# Bpod_PortBreakout_r1.net
KiCad netlist of a schematic drawn in EAGLE
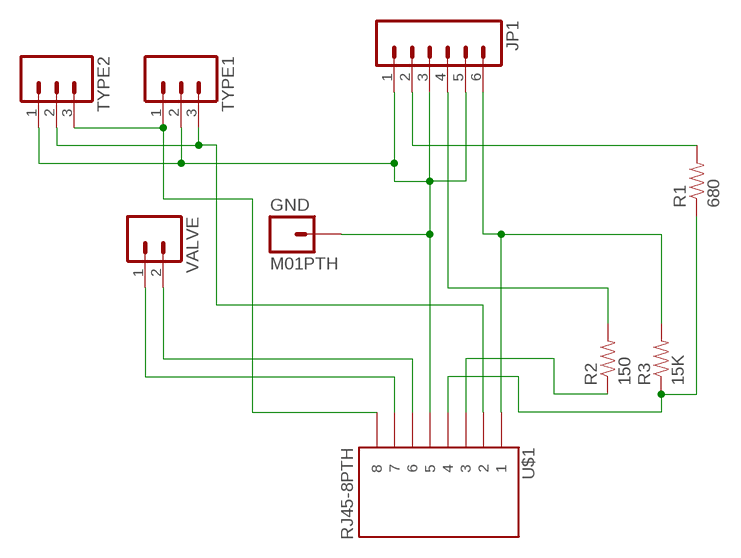
[diagram p0: schematic, sheet 1]

(export (version "E")
  (design (tool "Eeschema 10.0.6"))
  (components
    (comp (ref "GND")
      (value "M01PTH")
      (footprint "eagle-import:1X01")
      (libsource (lib "eagle-import") (part "M01PTH"))
    )
    (comp (ref "JP1")
      (value "M063.5MM-6")
      (footprint "eagle-import:SCREWTERMINAL-3.5MM-6")
      (libsource (lib "eagle-import") (part "M063.5MM-6"))
    )
    (comp (ref "R1")
      (value "680")
      (footprint "eagle-import:AXIAL-0.4")
      (libsource (lib "eagle-import") (part "RESISTORPTH-1/4W"))
    )
    (comp (ref "R2")
      (value "150")
      (footprint "eagle-import:AXIAL-0.4")
      (libsource (lib "eagle-import") (part "RESISTORPTH-1/4W"))
    )
    (comp (ref "R3")
      (value "15K")
      (footprint "eagle-import:AXIAL-0.4")
      (libsource (lib "eagle-import") (part "RESISTORPTH-1/4W"))
    )
    (comp (ref "TYPE1")
      (value "M03PTH")
      (footprint "eagle-import:1X03")
      (libsource (lib "eagle-import") (part "M03PTH"))
    )
    (comp (ref "TYPE2")
      (value "M03PTH")
      (footprint "eagle-import:1X03")
      (libsource (lib "eagle-import") (part "M03PTH"))
    )
    (comp (ref "U$1")
      (value "RJ45-8PTH")
      (footprint "eagle-import:RJ45-8")
      (libsource (lib "eagle-import") (part "RJ45-8PTH"))
    )
    (comp (ref "VALVE")
      (value "M023.5MM_LOCK")
      (footprint "eagle-import:SCREWTERMINAL-3.5MM-2_LOCK")
      (libsource (lib "eagle-import") (part "M023.5MM_LOCK"))
    )
  )
  (nets
    (net (code "1") (name "Net-(GND-Pad1)") (class "Default")
      (node (ref "GND") (pin "1") (pinfunction "1_1") (pintype "passive"))
      (node (ref "JP1") (pin "1") (pinfunction "1_1") (pintype "passive"))
      (node (ref "JP1") (pin "3") (pinfunction "3_3") (pintype "passive"))
      (node (ref "JP1") (pin "5") (pinfunction "5_5") (pintype "passive"))
      (node (ref "TYPE1") (pin "2") (pinfunction "2_2") (pintype "passive"))
      (node (ref "TYPE2") (pin "1") (pinfunction "1_1") (pintype "passive"))
      (node (ref "U$1") (pin "5") (pinfunction "5_5") (pintype "bidirectional"))
    )
    (net (code "2") (name "Net-(R1-1)") (class "Default")
      (node (ref "R1") (pin "P$1") (pinfunction "1_P$1") (pintype "passive"))
      (node (ref "R3") (pin "P$1") (pinfunction "1_P$1") (pintype "passive"))
      (node (ref "U$1") (pin "4") (pinfunction "4_4") (pintype "bidirectional"))
    )
    (net (code "3") (name "Net-(R1-2)") (class "Default")
      (node (ref "JP1") (pin "2") (pinfunction "2_2") (pintype "passive"))
      (node (ref "R1") (pin "P$2") (pinfunction "2_P$2") (pintype "passive"))
    )
    (net (code "4") (name "Net-(R2-1)") (class "Default")
      (node (ref "R2") (pin "P$1") (pinfunction "1_P$1") (pintype "passive"))
      (node (ref "U$1") (pin "3") (pinfunction "3_3") (pintype "bidirectional"))
    )
    (net (code "5") (name "Net-(R2-2)") (class "Default")
      (node (ref "JP1") (pin "4") (pinfunction "4_4") (pintype "passive"))
      (node (ref "R2") (pin "P$2") (pinfunction "2_P$2") (pintype "passive"))
    )
    (net (code "6") (name "Net-(R3-2)") (class "Default")
      (node (ref "JP1") (pin "6") (pinfunction "6_6") (pintype "passive"))
      (node (ref "R3") (pin "P$2") (pinfunction "2_P$2") (pintype "passive"))
      (node (ref "U$1") (pin "1") (pinfunction "1_1") (pintype "bidirectional"))
    )
    (net (code "7") (name "Net-(TYPE1-Pad1)") (class "Default")
      (node (ref "TYPE1") (pin "1") (pinfunction "1_1") (pintype "passive"))
      (node (ref "TYPE2") (pin "3") (pinfunction "3_3") (pintype "passive"))
      (node (ref "U$1") (pin "8") (pinfunction "8_8") (pintype "bidirectional"))
    )
    (net (code "8") (name "Net-(TYPE1-Pad3)") (class "Default")
      (node (ref "TYPE1") (pin "3") (pinfunction "3_3") (pintype "passive"))
      (node (ref "TYPE2") (pin "2") (pinfunction "2_2") (pintype "passive"))
      (node (ref "U$1") (pin "2") (pinfunction "2_2") (pintype "bidirectional"))
    )
    (net (code "9") (name "Net-(U$1-Pad6)") (class "Default")
      (node (ref "U$1") (pin "6") (pinfunction "6_6") (pintype "bidirectional"))
      (node (ref "VALVE") (pin "2") (pinfunction "2_2") (pintype "passive"))
    )
    (net (code "10") (name "Net-(U$1-Pad7)") (class "Default")
      (node (ref "U$1") (pin "7") (pinfunction "7_7") (pintype "bidirectional"))
      (node (ref "VALVE") (pin "1") (pinfunction "1_1") (pintype "passive"))
    )
  )
)
